# shield_SIP800L.net
KiCad netlist of a schematic drawn in EAGLE
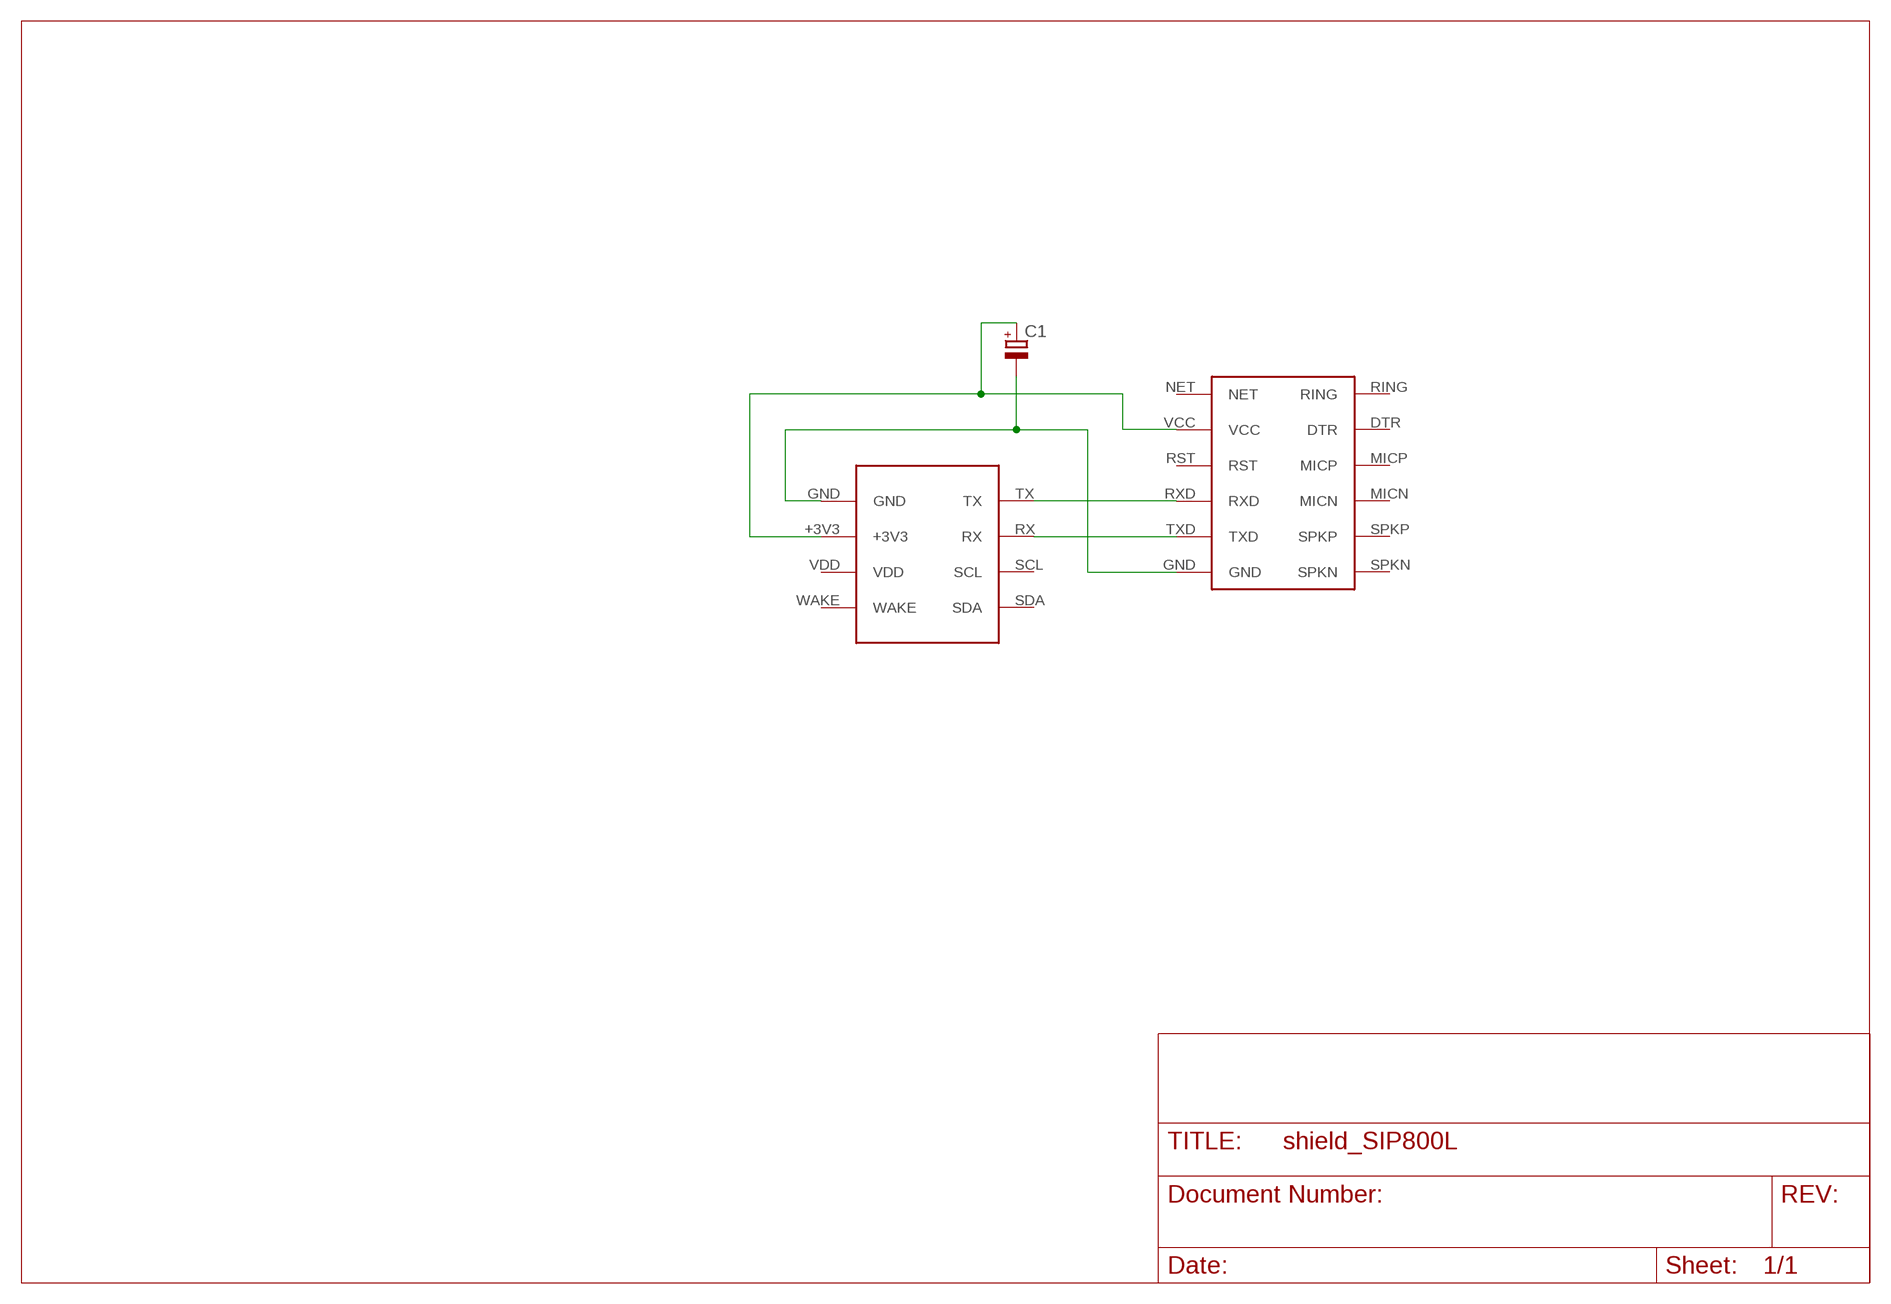
[diagram p0: schematic, sheet 1]

(export (version "E")
  (design (tool "Eeschema 10.0.6"))
  (components
    (comp (ref "C1")
      (value "CPOL-EUE5-13")
      (footprint "eagle-import:E5-13")
      (libsource (lib "eagle-import") (part "CPOL-EUE5-13"))
    )
    (comp (ref "U$1")
      (value "SHIELD")
      (footprint "eagle-import:SHIELD")
      (libsource (lib "eagle-import") (part "SHIELD"))
    )
    (comp (ref "U$6")
      (value "SIM800L")
      (footprint "eagle-import:SIM800L")
      (libsource (lib "eagle-import") (part "SIM800L"))
    )
  )
  (nets
    (net (code "1") (name "/VDD") (class "Default")
      (node (ref "U$1") (pin "VDD") (pinfunction "VDD_VDD") (pintype "power_in"))
    )
    (net (code "2") (name "Net-(C1-Pad+)") (class "Default")
      (node (ref "C1") (pin "+") (pinfunction "+_+") (pintype "passive"))
      (node (ref "U$1") (pin "+3V3") (pinfunction "+3V3_+3V3") (pintype "power_in"))
      (node (ref "U$6") (pin "VCC") (pinfunction "VCC_VCC") (pintype "bidirectional"))
    )
    (net (code "3") (name "Net-(C1-Pad-)") (class "Default")
      (node (ref "C1") (pin "-") (pinfunction "-_-") (pintype "passive"))
      (node (ref "U$1") (pin "GND") (pinfunction "GND_GND") (pintype "power_in"))
      (node (ref "U$6") (pin "GND") (pinfunction "GND_GND") (pintype "bidirectional"))
    )
    (net (code "4") (name "Net-(U$1-PadRX)") (class "Default")
      (node (ref "U$1") (pin "RX") (pinfunction "RX_RX") (pintype "input"))
      (node (ref "U$6") (pin "TXD") (pinfunction "TXD_TXD") (pintype "bidirectional"))
    )
    (net (code "5") (name "Net-(U$1-PadTX)") (class "Default")
      (node (ref "U$1") (pin "TX") (pinfunction "TX_TX") (pintype "output"))
      (node (ref "U$6") (pin "RXD") (pinfunction "RXD_RXD") (pintype "bidirectional"))
    )
    (net (code "6") (name "unconnected-(U$1-PadSCL)") (class "Default")
      (node (ref "U$1") (pin "SCL") (pinfunction "SCL_SCL") (pintype "output"))
    )
    (net (code "7") (name "unconnected-(U$1-PadSDA)") (class "Default")
      (node (ref "U$1") (pin "SDA") (pinfunction "SDA_SDA") (pintype "bidirectional"))
    )
    (net (code "8") (name "unconnected-(U$1-PadWAKE)") (class "Default")
      (node (ref "U$1") (pin "WAKE") (pinfunction "WAKE_WAKE") (pintype "output"))
    )
    (net (code "9") (name "unconnected-(U$6-PadDTR)") (class "Default")
      (node (ref "U$6") (pin "DTR") (pinfunction "DTR_DTR") (pintype "bidirectional"))
    )
    (net (code "10") (name "unconnected-(U$6-PadMICN)") (class "Default")
      (node (ref "U$6") (pin "MICN") (pinfunction "MICN_MICN") (pintype "bidirectional"))
    )
    (net (code "11") (name "unconnected-(U$6-PadMICP)") (class "Default")
      (node (ref "U$6") (pin "MICP") (pinfunction "MICP_MICP") (pintype "bidirectional"))
    )
    (net (code "12") (name "unconnected-(U$6-PadNET)") (class "Default")
      (node (ref "U$6") (pin "NET") (pinfunction "NET_NET") (pintype "bidirectional"))
    )
    (net (code "13") (name "unconnected-(U$6-PadRING)") (class "Default")
      (node (ref "U$6") (pin "RING") (pinfunction "RING_RING") (pintype "bidirectional"))
    )
    (net (code "14") (name "unconnected-(U$6-PadRST)") (class "Default")
      (node (ref "U$6") (pin "RST") (pinfunction "RST_RST") (pintype "bidirectional"))
    )
    (net (code "15") (name "unconnected-(U$6-PadSPKN)") (class "Default")
      (node (ref "U$6") (pin "SPKN") (pinfunction "SPKN_SPKN") (pintype "bidirectional"))
    )
    (net (code "16") (name "unconnected-(U$6-PadSPKP)") (class "Default")
      (node (ref "U$6") (pin "SPKP") (pinfunction "SPKP_SPKP") (pintype "bidirectional"))
    )
  )
)
